# Thermistor.net
KiCad netlist of a schematic drawn in Altium Designer
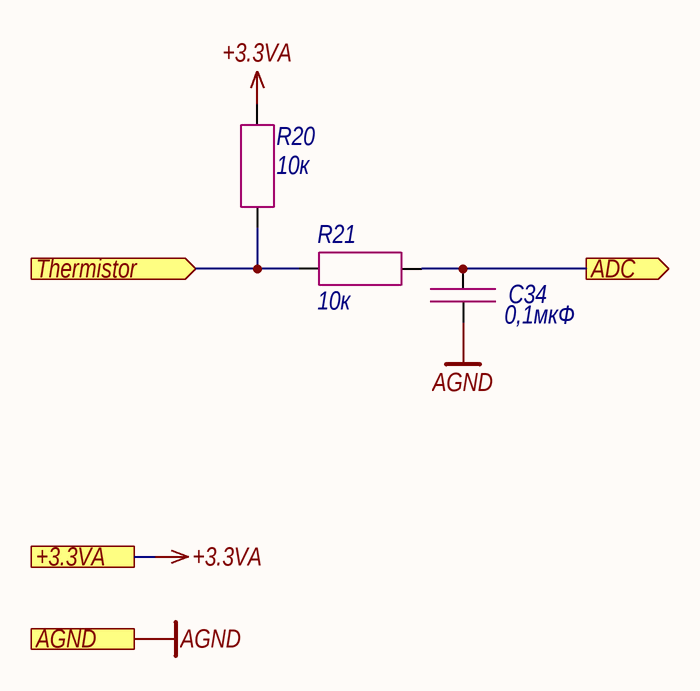
[diagram p0: Thermistor.SchDoc]

(export (version "E")
  (design (tool "Eeschema 10.0.6"))
  (components
    (comp (ref "C34")
      (value "0,1мкФ")
      (footprint "Pcb_library:CAP_0603")
      (fields (field (name "MANUFACTURER") "Murata"))
      (libsource (lib "Schem_library") (part "Capacitor"))
    )
    (comp (ref "R20")
      (value "10к")
      (footprint "Pcb_library:RES_0603")
      (fields (field (name "MANUFACTURER") "Yageo"))
      (libsource (lib "Schem_library") (part "Resistor"))
    )
    (comp (ref "R21")
      (value "10к")
      (footprint "Pcb_library:RES_0603")
      (fields (field (name "MANUFACTURER") "Yageo"))
      (libsource (lib "Schem_library") (part "Resistor"))
    )
  )
  (nets
    (net (code "1") (name "+3.3VA") (class "Default")
      (node (ref "R20") (pin "1") (pinfunction "1_1") (pintype "passive"))
    )
    (net (code "2") (name "/ADC") (class "Default")
      (node (ref "C34") (pin "1") (pinfunction "1_1") (pintype "passive"))
      (node (ref "R21") (pin "2") (pinfunction "2_2") (pintype "passive"))
    )
    (net (code "3") (name "/Thermistor") (class "Default")
      (node (ref "R20") (pin "2") (pinfunction "2_2") (pintype "passive"))
      (node (ref "R21") (pin "1") (pinfunction "1_1") (pintype "passive"))
    )
    (net (code "4") (name "AGND") (class "Default")
      (node (ref "C34") (pin "2") (pinfunction "2_2") (pintype "passive"))
    )
  )
)
